# hat_raspi_7segdis.net
KiCad netlist of a schematic drawn in EAGLE
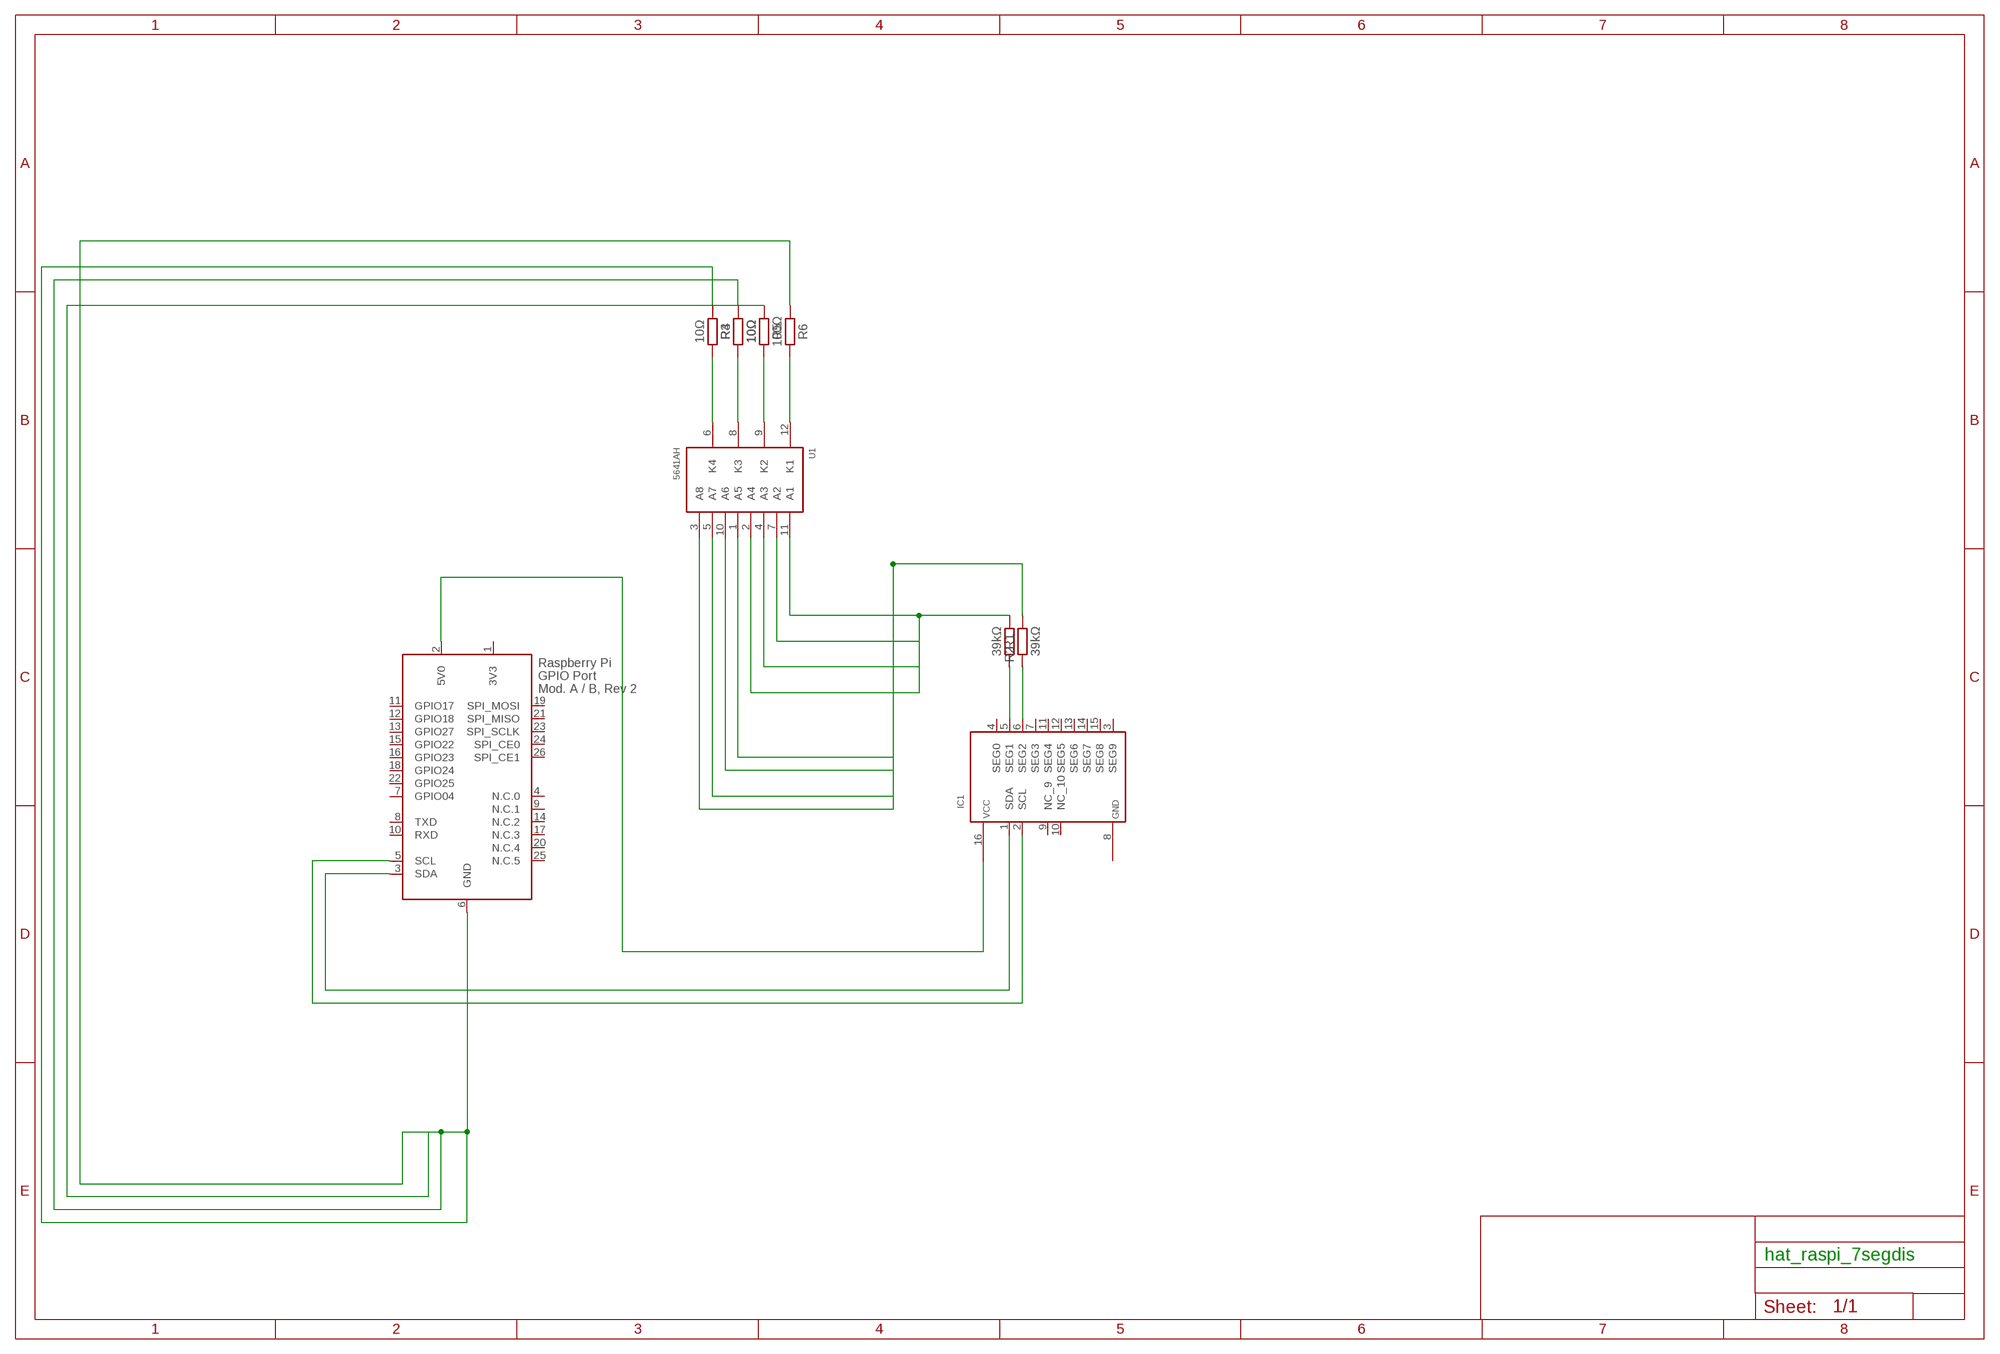
[diagram p0: schematic, sheet 1]

(export (version "E")
  (design (tool "Eeschema 10.0.6"))
  (components
    (comp (ref "IC1")
      (value "MAX6958")
      (footprint "eagle-import:QSOP16")
      (libsource (lib "eagle-import") (part "MAX6958"))
    )
    (comp (ref "R1")
      (value "39kΩ")
      (footprint "eagle-import:RESAD724W46L381D178B")
      (libsource (lib "eagle-import") (part "RAXIAL-7.2MM-PITCH_"))
    )
    (comp (ref "R2")
      (value "39kΩ")
      (footprint "eagle-import:RESAD724W46L381D178B")
      (libsource (lib "eagle-import") (part "RAXIAL-7.2MM-PITCH_"))
    )
    (comp (ref "R3")
      (value "10Ω")
      (footprint "eagle-import:RESAD724W46L381D178B")
      (libsource (lib "eagle-import") (part "RAXIAL-7.2MM-PITCH_"))
    )
    (comp (ref "R4")
      (value "10Ω")
      (footprint "eagle-import:RESAD724W46L381D178B")
      (libsource (lib "eagle-import") (part "RAXIAL-7.2MM-PITCH_"))
    )
    (comp (ref "R5")
      (value "10Ω")
      (footprint "eagle-import:RESAD724W46L381D178B")
      (libsource (lib "eagle-import") (part "RAXIAL-7.2MM-PITCH_"))
    )
    (comp (ref "R6")
      (value "100Ω")
      (footprint "eagle-import:RESAD724W46L381D178B")
      (libsource (lib "eagle-import") (part "RAXIAL-7.2MM-PITCH_"))
    )
    (comp (ref "U1")
      (value "5641AH")
      (footprint "eagle-import:5642AH")
      (libsource (lib "eagle-import") (part "5641AH"))
    )
    (comp (ref "X1")
      (value "RASPI_BOARD_AB_E2P")
      (footprint "eagle-import:RASPI_BOARD_AB_EDGES_2DRILL_PAD")
      (libsource (lib "eagle-import") (part "RASPI_BOARD_AB_E2P"))
    )
  )
  (nets
    (net (code "1") (name "/3V3") (class "Default")
      (node (ref "X1") (pin "1") (pinfunction "3V3_1") (pintype "power_in"))
    )
    (net (code "2") (name "/GND") (class "Default")
      (node (ref "IC1") (pin "8") (pinfunction "GND_8") (pintype "power_in"))
    )
    (net (code "3") (name "Net-(IC1-SCL)") (class "Default")
      (node (ref "IC1") (pin "2") (pinfunction "SCL_2") (pintype "input"))
      (node (ref "X1") (pin "5") (pinfunction "SCL_5") (pintype "bidirectional"))
    )
    (net (code "4") (name "Net-(IC1-SDA)") (class "Default")
      (node (ref "IC1") (pin "1") (pinfunction "SDA_1") (pintype "input"))
      (node (ref "X1") (pin "3") (pinfunction "SDA_3") (pintype "bidirectional"))
    )
    (net (code "5") (name "Net-(IC1-SEG1)") (class "Default")
      (node (ref "IC1") (pin "5") (pinfunction "SEG1_5") (pintype "output"))
      (node (ref "R2") (pin "2") (pinfunction "2_2") (pintype "passive"))
    )
    (net (code "6") (name "Net-(IC1-SEG2)") (class "Default")
      (node (ref "IC1") (pin "6") (pinfunction "SEG2_6") (pintype "output"))
      (node (ref "R1") (pin "1") (pinfunction "1_1") (pintype "passive"))
    )
    (net (code "7") (name "Net-(IC1-VCC)") (class "Default")
      (node (ref "IC1") (pin "16") (pinfunction "VCC_16") (pintype "power_in"))
      (node (ref "X1") (pin "2") (pinfunction "5V0_2") (pintype "power_in"))
    )
    (net (code "8") (name "Net-(U1-A1)") (class "Default")
      (node (ref "R2") (pin "1") (pinfunction "1_1") (pintype "passive"))
      (node (ref "U1") (pin "11") (pinfunction "A1_11") (pintype "bidirectional"))
      (node (ref "U1") (pin "2") (pinfunction "A4_2") (pintype "bidirectional"))
      (node (ref "U1") (pin "4") (pinfunction "A3_4") (pintype "bidirectional"))
      (node (ref "U1") (pin "7") (pinfunction "A2_7") (pintype "bidirectional"))
    )
    (net (code "9") (name "Net-(U1-A5)") (class "Default")
      (node (ref "R1") (pin "2") (pinfunction "2_2") (pintype "passive"))
      (node (ref "U1") (pin "1") (pinfunction "A5_1") (pintype "bidirectional"))
      (node (ref "U1") (pin "10") (pinfunction "A6_10") (pintype "bidirectional"))
      (node (ref "U1") (pin "3") (pinfunction "A8_3") (pintype "bidirectional"))
      (node (ref "U1") (pin "5") (pinfunction "A7_5") (pintype "bidirectional"))
    )
    (net (code "10") (name "Net-(U1-K1)") (class "Default")
      (node (ref "R6") (pin "2") (pinfunction "2_2") (pintype "passive"))
      (node (ref "U1") (pin "12") (pinfunction "K1_12") (pintype "bidirectional"))
    )
    (net (code "11") (name "Net-(U1-K2)") (class "Default")
      (node (ref "R5") (pin "2") (pinfunction "2_2") (pintype "passive"))
      (node (ref "U1") (pin "9") (pinfunction "K2_9") (pintype "bidirectional"))
    )
    (net (code "12") (name "Net-(U1-K3)") (class "Default")
      (node (ref "R3") (pin "1") (pinfunction "1_1") (pintype "passive"))
      (node (ref "U1") (pin "8") (pinfunction "K3_8") (pintype "bidirectional"))
    )
    (net (code "13") (name "Net-(U1-K4)") (class "Default")
      (node (ref "R4") (pin "2") (pinfunction "2_2") (pintype "passive"))
      (node (ref "U1") (pin "6") (pinfunction "K4_6") (pintype "bidirectional"))
    )
    (net (code "14") (name "Net-(X1-GND)") (class "Default")
      (node (ref "R3") (pin "2") (pinfunction "2_2") (pintype "passive"))
      (node (ref "R4") (pin "1") (pinfunction "1_1") (pintype "passive"))
      (node (ref "R5") (pin "1") (pinfunction "1_1") (pintype "passive"))
      (node (ref "R6") (pin "1") (pinfunction "1_1") (pintype "passive"))
      (node (ref "X1") (pin "6") (pinfunction "GND_6") (pintype "power_in"))
    )
    (net (code "15") (name "unconnected-(IC1-NC_9-Pad9)") (class "Default")
      (node (ref "IC1") (pin "9") (pinfunction "NC_9_9") (pintype "output"))
    )
    (net (code "16") (name "unconnected-(IC1-NC_10-Pad10)") (class "Default")
      (node (ref "IC1") (pin "10") (pinfunction "NC_10_10") (pintype "output"))
    )
    (net (code "17") (name "unconnected-(IC1-SEG0-Pad4)") (class "Default")
      (node (ref "IC1") (pin "4") (pinfunction "SEG0_4") (pintype "output"))
    )
    (net (code "18") (name "unconnected-(IC1-SEG3-Pad7)") (class "Default")
      (node (ref "IC1") (pin "7") (pinfunction "SEG3_7") (pintype "output"))
    )
    (net (code "19") (name "unconnected-(IC1-SEG4-Pad11)") (class "Default")
      (node (ref "IC1") (pin "11") (pinfunction "SEG4_11") (pintype "output"))
    )
    (net (code "20") (name "unconnected-(IC1-SEG5-Pad12)") (class "Default")
      (node (ref "IC1") (pin "12") (pinfunction "SEG5_12") (pintype "output"))
    )
    (net (code "21") (name "unconnected-(IC1-SEG6-Pad13)") (class "Default")
      (node (ref "IC1") (pin "13") (pinfunction "SEG6_13") (pintype "output"))
    )
    (net (code "22") (name "unconnected-(IC1-SEG7-Pad14)") (class "Default")
      (node (ref "IC1") (pin "14") (pinfunction "SEG7_14") (pintype "output"))
    )
    (net (code "23") (name "unconnected-(IC1-SEG8-Pad15)") (class "Default")
      (node (ref "IC1") (pin "15") (pinfunction "SEG8_15") (pintype "output"))
    )
    (net (code "24") (name "unconnected-(IC1-SEG9-Pad3)") (class "Default")
      (node (ref "IC1") (pin "3") (pinfunction "SEG9_3") (pintype "output"))
    )
    (net (code "25") (name "unconnected-(X1-GPIO04-Pad7)") (class "Default")
      (node (ref "X1") (pin "7") (pinfunction "GPIO04_7") (pintype "bidirectional"))
    )
    (net (code "26") (name "unconnected-(X1-GPIO17-Pad11)") (class "Default")
      (node (ref "X1") (pin "11") (pinfunction "GPIO17_11") (pintype "bidirectional"))
    )
    (net (code "27") (name "unconnected-(X1-GPIO18-Pad12)") (class "Default")
      (node (ref "X1") (pin "12") (pinfunction "GPIO18_12") (pintype "bidirectional"))
    )
    (net (code "28") (name "unconnected-(X1-GPIO22-Pad15)") (class "Default")
      (node (ref "X1") (pin "15") (pinfunction "GPIO22_15") (pintype "bidirectional"))
    )
    (net (code "29") (name "unconnected-(X1-GPIO23-Pad16)") (class "Default")
      (node (ref "X1") (pin "16") (pinfunction "GPIO23_16") (pintype "bidirectional"))
    )
    (net (code "30") (name "unconnected-(X1-GPIO24-Pad18)") (class "Default")
      (node (ref "X1") (pin "18") (pinfunction "GPIO24_18") (pintype "bidirectional"))
    )
    (net (code "31") (name "unconnected-(X1-GPIO25-Pad22)") (class "Default")
      (node (ref "X1") (pin "22") (pinfunction "GPIO25_22") (pintype "bidirectional"))
    )
    (net (code "32") (name "unconnected-(X1-GPIO27-Pad13)") (class "Default")
      (node (ref "X1") (pin "13") (pinfunction "GPIO27_13") (pintype "bidirectional"))
    )
    (net (code "33") (name "unconnected-(X1-N.C.0-Pad4)") (class "Default")
      (node (ref "X1") (pin "4") (pinfunction "N.C.0_4") (pintype "no_connect"))
    )
    (net (code "34") (name "unconnected-(X1-N.C.1-Pad9)") (class "Default")
      (node (ref "X1") (pin "9") (pinfunction "N.C.1_9") (pintype "no_connect"))
    )
    (net (code "35") (name "unconnected-(X1-N.C.2-Pad14)") (class "Default")
      (node (ref "X1") (pin "14") (pinfunction "N.C.2_14") (pintype "no_connect"))
    )
    (net (code "36") (name "unconnected-(X1-N.C.3-Pad17)") (class "Default")
      (node (ref "X1") (pin "17") (pinfunction "N.C.3_17") (pintype "no_connect"))
    )
    (net (code "37") (name "unconnected-(X1-N.C.4-Pad20)") (class "Default")
      (node (ref "X1") (pin "20") (pinfunction "N.C.4_20") (pintype "no_connect"))
    )
    (net (code "38") (name "unconnected-(X1-N.C.5-Pad25)") (class "Default")
      (node (ref "X1") (pin "25") (pinfunction "N.C.5_25") (pintype "no_connect"))
    )
    (net (code "39") (name "unconnected-(X1-RXD-Pad10)") (class "Default")
      (node (ref "X1") (pin "10") (pinfunction "RXD_10") (pintype "bidirectional"))
    )
    (net (code "40") (name "unconnected-(X1-SPI_CE0-Pad24)") (class "Default")
      (node (ref "X1") (pin "24") (pinfunction "SPI_CE0_24") (pintype "bidirectional"))
    )
    (net (code "41") (name "unconnected-(X1-SPI_CE1-Pad26)") (class "Default")
      (node (ref "X1") (pin "26") (pinfunction "SPI_CE1_26") (pintype "bidirectional"))
    )
    (net (code "42") (name "unconnected-(X1-SPI_MISO-Pad21)") (class "Default")
      (node (ref "X1") (pin "21") (pinfunction "SPI_MISO_21") (pintype "bidirectional"))
    )
    (net (code "43") (name "unconnected-(X1-SPI_MOSI-Pad19)") (class "Default")
      (node (ref "X1") (pin "19") (pinfunction "SPI_MOSI_19") (pintype "bidirectional"))
    )
    (net (code "44") (name "unconnected-(X1-SPI_SCLK-Pad23)") (class "Default")
      (node (ref "X1") (pin "23") (pinfunction "SPI_SCLK_23") (pintype "bidirectional"))
    )
    (net (code "45") (name "unconnected-(X1-TXD-Pad8)") (class "Default")
      (node (ref "X1") (pin "8") (pinfunction "TXD_8") (pintype "bidirectional"))
    )
  )
)
